# HRT1.net
KiCad netlist of a schematic drawn in Altium Designer
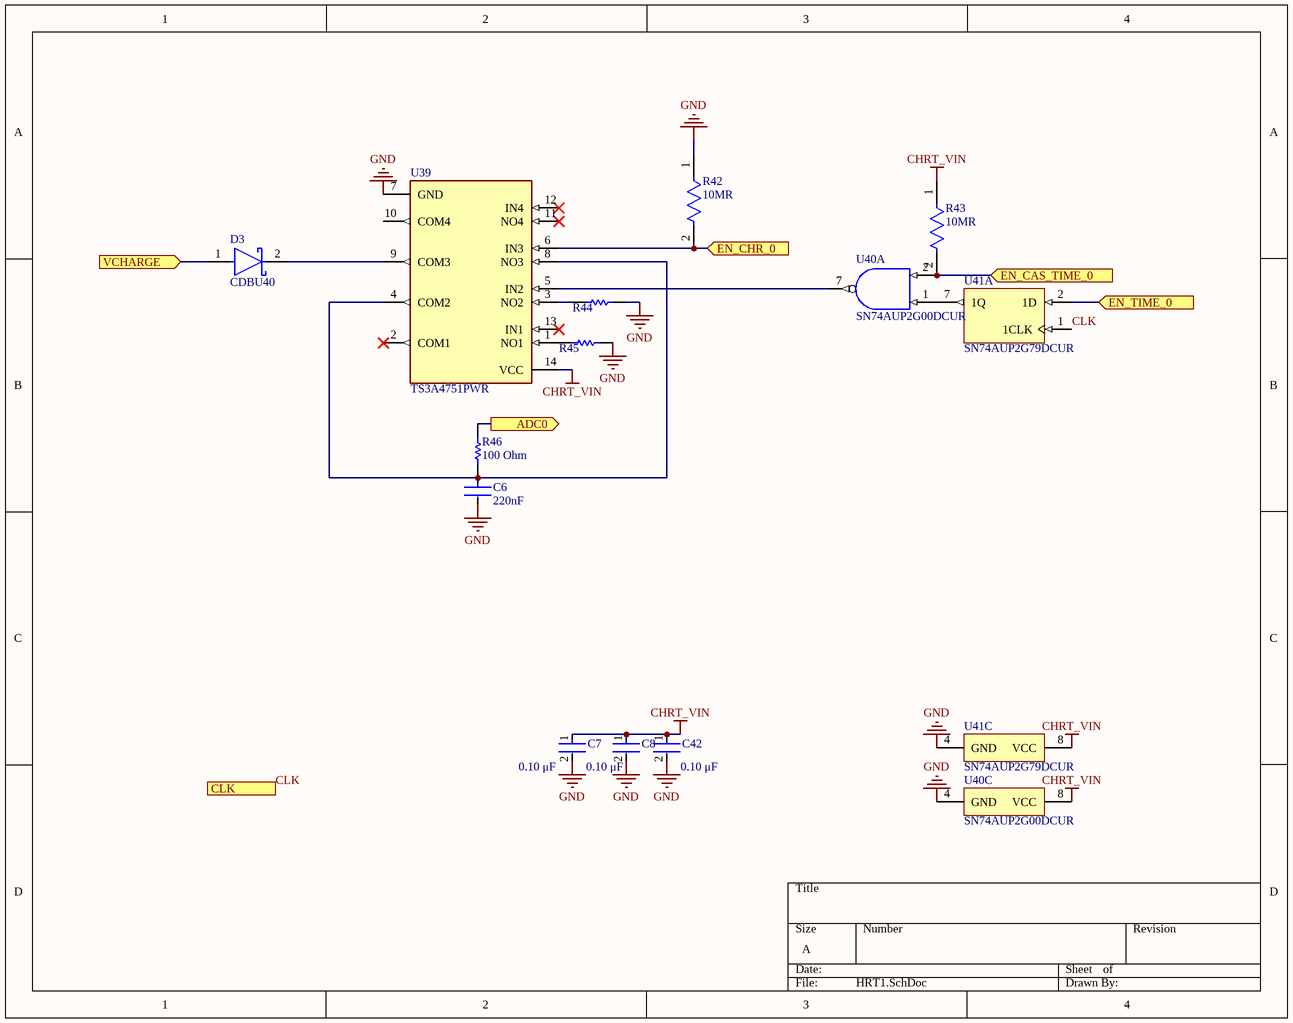
[diagram p0: HRT1.SchDoc]

(export (version "E")
  (design (tool "Eeschema 10.0.6"))
  (components
    (comp (ref "C6")
      (value "GRM155R71C224KA12D")
      (footprint "FP-GRM155-0_05-IPC_C")
      (description "Chip Multilayer Ceramic Capacitors for General Purpose, 0402, 0.22uF, X7R, 15%, 10%, 16V")
      (fields
        (field (name "CAPACITANCE") "220nF")
        (field (name "VOLTAGE") "16V")
        (field (name "TOLERANCE") "10%")
      )
      (libsource (lib "Altium Content Vault") (part "02cd4be3c70576c341d710602a673aa"))
    )
    (comp (ref "C7")
      (value "C0402C104K8PACTU")
      (footprint "FP-C0402-BB-MFG")
      (description "CAP CER 0.1UF 10V X5R 0402")
      (fields
        (field (name "CAPACITANCE") "0.10 μF")
        (field (name "MANUFACTURER") "Kemet")
        (field (name "TOLERANCE") "0.1")
      )
      (libsource (lib "Altium Content Vault") (part "b4654b650e69147ec39a6b967a45e02"))
    )
    (comp (ref "C8")
      (value "C0402C104K8PACTU")
      (footprint "FP-C0402-BB-MFG")
      (description "CAP CER 0.1UF 10V X5R 0402")
      (fields
        (field (name "CAPACITANCE") "0.10 μF")
        (field (name "MANUFACTURER") "Kemet")
        (field (name "TOLERANCE") "0.1")
      )
      (libsource (lib "Altium Content Vault") (part "b4654b650e69147ec39a6b967a45e02"))
    )
    (comp (ref "C42")
      (value "C0402C104K8PACTU")
      (footprint "FP-C0402-BB-MFG")
      (description "CAP CER 0.1UF 10V X5R 0402")
      (fields
        (field (name "CAPACITANCE") "0.10 μF")
        (field (name "MANUFACTURER") "Kemet")
        (field (name "TOLERANCE") "0.1")
      )
      (libsource (lib "Altium Content Vault") (part "b4654b650e69147ec39a6b967a45e02"))
    )
    (comp (ref "D3")
      (value "CDBU40")
      (footprint "FP-S8-V-3880_02-001-MFG")
      (description "DIODE SCHOTTKY 40V 120MA SOD523")
      (fields
        (field (name "OCTOPART") "https://octopart.com/bas40-02v-v-g-08-vishay-44351221")
        (field (name "MANUFACTURER") "Vishay")
      )
      (libsource (lib "Altium Content Vault") (part "360ad2f4ac25a952324d13796385471"))
    )
    (comp (ref "R42")
      (value "CRCW040210M0JNED")
      (footprint "FP-CRCW0402-e3-IPC_C")
      (description "RES Thick Film, 10MΩ, 5%, 0.063W, 200ppm/°C, 0402")
      (fields (field (name "TOLERANCE") "5%") (field (name "RESISTANCE") "10MR"))
      (libsource (lib "Altium Content Vault") (part "1029c3af85768c4190bb7ad29bc67b5"))
    )
    (comp (ref "R43")
      (value "CRCW040210M0JNED")
      (footprint "FP-CRCW0402-e3-IPC_C")
      (description "RES Thick Film, 10MΩ, 5%, 0.063W, 200ppm/°C, 0402")
      (fields (field (name "TOLERANCE") "5%") (field (name "RESISTANCE") "10MR"))
      (libsource (lib "Altium Content Vault") (part "1029c3af85768c4190bb7ad29bc67b5"))
    )
    (comp (ref "R44")
      (value "CRCW040222R0FKED")
      (footprint "RESC1005X40X25LL05T05")
      (fields (field (name "MANUFACTURER") "Vishay Dale"))
      (libsource (lib "Altium Content Vault") (part "RES"))
    )
    (comp (ref "R45")
      (value "CRCW040222R0FKED")
      (footprint "RESC1005X40X25LL05T05")
      (fields (field (name "MANUFACTURER") "Vishay Dale"))
      (libsource (lib "Altium Content Vault") (part "RES"))
    )
    (comp (ref "R46")
      (value "ERJ-2RKF1000X")
      (footprint "RESC1005X40X25LL05T05")
      (description "Chip Resistor, 100 Ohm, +/- 1%, 100 mW, -55 to 155 degC, 0402 (1005 Metric), RoHS, Tape and Reel")
      (fields
        (field (name "MANUFACTURER") "Basic Passives")
        (field (name "TOLERANCE") "1%")
        (field (name "RESISTANCE") "100 Ohm")
      )
      (libsource (lib "Altium Content Vault") (part "RES-2"))
    )
    (comp (ref "U39")
      (value "TS3A4751PWR")
      (footprint "FP-PW0014A-IPC_C")
      (description "IC SWITCH QUAD SPST 14TSSOP")
      (libsource (lib "Altium Content Vault") (part "75fdcfb842d41a92b92a478e82e68ae"))
    )
    (comp (ref "U40")
      (value "SN74AUP2G00DCUR")
      (footprint "DCU0008A_L")
      (description "Low-Power Dual 2-Input Positive-NAND Gate, DCU0008A, LARGE T&R")
      (fields
        (field (name "GENERIC PART NUMBER") "SN74AUP2G00")
        (field (name "MANUFACTURER") "Texas Instruments")
      )
      (libsource (lib "Altium Content Vault") (part "TI-SN74XXX2GXXX-8"))
    )
    (comp (ref "U41")
      (value "SN74AUP2G79DCUR")
      (footprint "DCU0008A_L")
      (description "Low-Power Dual Positive-Edge-Triggered D-Type Flip-Flop, DCU0008A, LARGE T&R")
      (fields
        (field (name "MANUFACTURER") "Texas Instruments")
        (field (name "GENERIC PART NUMBER") "SN74AUP2G79")
      )
      (libsource (lib "Altium Content Vault") (part "TI-SN74XXX2G79-8_A"))
    )
  )
  (nets
    (net (code "1") (name "/ADC0") (class "Default")
      (node (ref "R46") (pin "2") (pinfunction "2_2") (pintype "passive"))
    )
    (net (code "2") (name "/CLK") (class "Default")
      (node (ref "U41") (pin "1") (pinfunction "1CLK_1") (pintype "input"))
    )
    (net (code "3") (name "/EN_CAS_TIME_0") (class "Default")
      (node (ref "R43") (pin "2") (pinfunction "2_2") (pintype "passive"))
      (node (ref "U40") (pin "2") (pinfunction "1B_2") (pintype "input"))
    )
    (net (code "4") (name "/EN_CHR_0") (class "Default")
      (node (ref "R42") (pin "2") (pinfunction "2_2") (pintype "passive"))
      (node (ref "U39") (pin "6") (pinfunction "IN3_6") (pintype "input"))
    )
    (net (code "5") (name "/EN_TIME_0") (class "Default")
      (node (ref "U41") (pin "2") (pinfunction "1D_2") (pintype "input"))
    )
    (net (code "6") (name "/VCHARGE") (class "Default")
      (node (ref "D3") (pin "1") (pinfunction "A_1") (pintype "passive"))
    )
    (net (code "7") (name "CHRT_VIN") (class "Default")
      (node (ref "C42") (pin "1") (pinfunction "1_1") (pintype "passive"))
      (node (ref "C7") (pin "1") (pinfunction "1_1") (pintype "passive"))
      (node (ref "C8") (pin "1") (pinfunction "1_1") (pintype "passive"))
      (node (ref "R43") (pin "1") (pinfunction "1_1") (pintype "passive"))
      (node (ref "U39") (pin "14") (pinfunction "VCC_14") (pintype "power_in"))
      (node (ref "U40") (pin "8") (pinfunction "VCC_8") (pintype "power_in"))
      (node (ref "U41") (pin "8") (pinfunction "VCC_8") (pintype "power_in"))
    )
    (net (code "8") (name "GND") (class "Default")
      (node (ref "C42") (pin "2") (pinfunction "2_2") (pintype "passive"))
      (node (ref "C6") (pin "2") (pinfunction "2_2") (pintype "passive"))
      (node (ref "C7") (pin "2") (pinfunction "2_2") (pintype "passive"))
      (node (ref "C8") (pin "2") (pinfunction "2_2") (pintype "passive"))
      (node (ref "R42") (pin "1") (pinfunction "1_1") (pintype "passive"))
      (node (ref "R44") (pin "2") (pinfunction "2_2") (pintype "passive"))
      (node (ref "R45") (pin "2") (pinfunction "2_2") (pintype "passive"))
      (node (ref "U39") (pin "7") (pinfunction "GND_7") (pintype "power_in"))
      (node (ref "U40") (pin "4") (pinfunction "GND_4") (pintype "power_in"))
      (node (ref "U41") (pin "4") (pinfunction "GND_4") (pintype "power_in"))
    )
    (net (code "9") (name "Net-(D3-C)") (class "Default")
      (node (ref "D3") (pin "2") (pinfunction "C_2") (pintype "passive"))
      (node (ref "U39") (pin "9") (pinfunction "COM3_9") (pintype "output"))
    )
    (net (code "10") (name "Net-(U39-COM2)") (class "Default")
      (node (ref "C6") (pin "1") (pinfunction "1_1") (pintype "passive"))
      (node (ref "R46") (pin "1") (pinfunction "1_1") (pintype "passive"))
      (node (ref "U39") (pin "4") (pinfunction "COM2_4") (pintype "output"))
      (node (ref "U39") (pin "8") (pinfunction "NO3_8") (pintype "input"))
    )
    (net (code "11") (name "Net-(U39-IN2)") (class "Default")
      (node (ref "U39") (pin "5") (pinfunction "IN2_5") (pintype "input"))
      (node (ref "U40") (pin "7") (pinfunction "1Y_7") (pintype "output"))
    )
    (net (code "12") (name "Net-(U39-NO1)") (class "Default")
      (node (ref "R45") (pin "1") (pinfunction "1_1") (pintype "passive"))
      (node (ref "U39") (pin "1") (pinfunction "NO1_1") (pintype "input"))
    )
    (net (code "13") (name "Net-(U39-NO2)") (class "Default")
      (node (ref "R44") (pin "1") (pinfunction "1_1") (pintype "passive"))
      (node (ref "U39") (pin "3") (pinfunction "NO2_3") (pintype "input"))
    )
    (net (code "14") (name "Net-(U40A-1A)") (class "Default")
      (node (ref "U40") (pin "1") (pinfunction "1A_1") (pintype "input"))
      (node (ref "U41") (pin "7") (pinfunction "1Q_7") (pintype "output"))
    )
    (net (code "15") (name "unconnected-(U39-COM1-Pad2)") (class "Default")
      (node (ref "U39") (pin "2") (pinfunction "COM1_2") (pintype "output+no_connect"))
    )
    (net (code "16") (name "unconnected-(U39-COM4-Pad10)") (class "Default")
      (node (ref "U39") (pin "10") (pinfunction "COM4_10") (pintype "output"))
    )
    (net (code "17") (name "unconnected-(U39-IN1-Pad13)") (class "Default")
      (node (ref "U39") (pin "13") (pinfunction "IN1_13") (pintype "input+no_connect"))
    )
    (net (code "18") (name "unconnected-(U39-IN4-Pad12)") (class "Default")
      (node (ref "U39") (pin "12") (pinfunction "IN4_12") (pintype "input+no_connect"))
    )
    (net (code "19") (name "unconnected-(U39-NO4-Pad11)") (class "Default")
      (node (ref "U39") (pin "11") (pinfunction "NO4_11") (pintype "input+no_connect"))
    )
  )
)
